# sensorion_board.net
KiCad netlist of a schematic drawn in Altium Designer
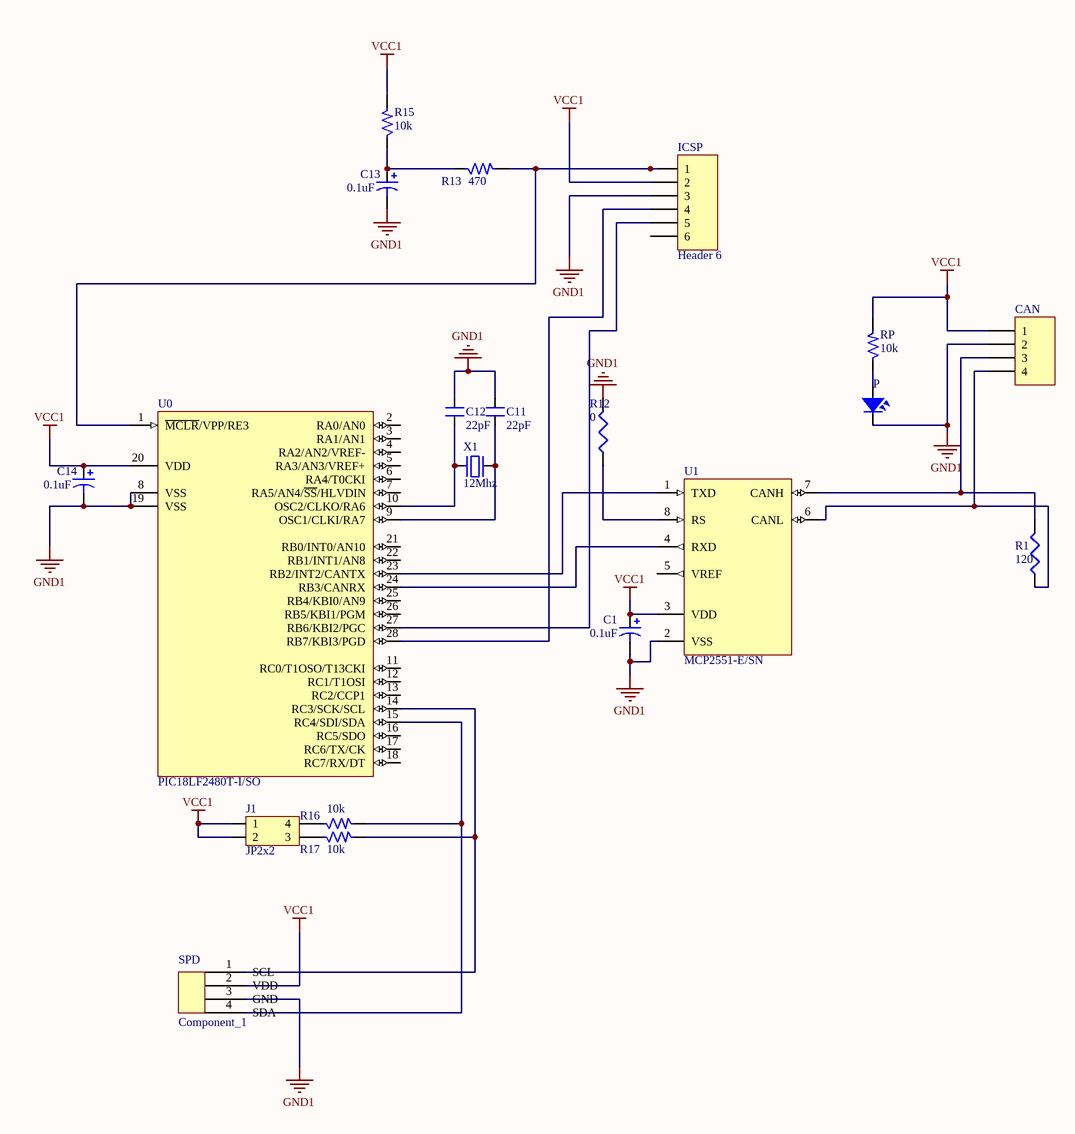
[diagram p0: sensorion_board.SchDoc]

(export (version "E")
  (design (tool "Eeschema 10.0.6"))
  (components
    (comp (ref "C1")
      (value "0.1uF")
      (footprint "C0805")
      (description "Polarized Capacitor (Surface Mount)")
      (fields (field (name "Comment") "Cap Pol3") (field (name "PUBLISHER") "Altium Limited"))
      (libsource (lib "Miscellaneous Devices") (part "Cap Pol3"))
    )
    (comp (ref "C11")
      (value "22pF")
      (footprint "CN1")
      (description "Cremic For Xtal 1pF => 100pF")
      (libsource (lib "electronicvn-library1") (part "CN0"))
    )
    (comp (ref "C12")
      (value "22pF")
      (footprint "CN1")
      (description "Cremic For Xtal 1pF => 100pF")
      (libsource (lib "electronicvn-library1") (part "CN0"))
    )
    (comp (ref "C13")
      (value "0.1uF")
      (footprint "C0805")
      (description "Polarized Capacitor (Surface Mount)")
      (fields (field (name "Comment") "Cap Pol3") (field (name "PUBLISHER") "Altium Limited"))
      (libsource (lib "Miscellaneous Devices") (part "Cap Pol3"))
    )
    (comp (ref "C14")
      (value "0.1uF")
      (footprint "C0805")
      (description "Polarized Capacitor (Surface Mount)")
      (fields (field (name "Comment") "Cap Pol3") (field (name "PUBLISHER") "Altium Limited"))
      (libsource (lib "Miscellaneous Devices") (part "Cap Pol3"))
    )
    (comp (ref "CAN")
      (value "Header 4")
      (footprint "HDR1X4")
      (description "Header, 4-Pin")
      (fields (field (name "PUBLISHER") "Altium Limited"))
      (libsource (lib "Miscellaneous Connectors") (part "Header 4"))
    )
    (comp (ref "ICSP")
      (value "Header 6")
      (footprint "HDR1X6")
      (description "Header, 6-Pin")
      (fields (field (name "PUBLISHER") "Altium Limited"))
      (libsource (lib "Miscellaneous Connectors") (part "Header 6"))
    )
    (comp (ref "J1")
      (value "JP2x2")
      (footprint "JP2-C2T")
      (description "WR-PHD 2.54 mm Dual Socket Header")
      (fields
        (field (name "MANUFACTURER") "Würth Elektronik eiSos GmbH")
        (field (name "PARTNO") "61300421821")
        (field (name "CREATED BY") "Karrer Zheng")
      )
      (libsource (lib "LIBRARY") (part "JP2x2"))
    )
    (comp (ref "P")
      (value "LED")
      (footprint "LED-3MM-YELLOW")
      (description "LED Single colour Green and Red")
      (libsource (lib "LIBRARY") (part "LED"))
    )
    (comp (ref "R1")
      (value "120")
      (footprint "J1-0603")
      (description "Resistor")
      (fields (field (name "Comment") "Res3") (field (name "PUBLISHER") "Altium Limited"))
      (libsource (lib "Miscellaneous Devices") (part "Res3"))
    )
    (comp (ref "R12")
      (value "0")
      (footprint "J1-0603")
      (description "Resistor")
      (fields (field (name "Comment") "Res3") (field (name "PUBLISHER") "Altium Limited"))
      (libsource (lib "Miscellaneous Devices") (part "Res3"))
    )
    (comp (ref "R13")
      (value "470")
      (footprint "SM-RES-1206")
      (description "Resistor 1/4W")
      (libsource (lib "electronicvn-library1") (part "R"))
    )
    (comp (ref "R15")
      (value "10k")
      (footprint "SM-RES-1206")
      (description "Resistor 1/4W")
      (libsource (lib "electronicvn-library1") (part "R"))
    )
    (comp (ref "R16")
      (value "10k")
      (footprint "SM-RES-1206")
      (description "Resistor 1/4W")
      (libsource (lib "electronicvn-library1") (part "R"))
    )
    (comp (ref "R17")
      (value "10k")
      (footprint "SM-RES-1206")
      (description "Resistor 1/4W")
      (libsource (lib "electronicvn-library1") (part "R"))
    )
    (comp (ref "RP")
      (value "10k")
      (footprint "SM-RES-1206")
      (description "Resistor 1/4W")
      (libsource (lib "electronicvn-library1") (part "R"))
    )
    (comp (ref "SPD")
      (value "Component_1")
      (footprint "PCBComponent_1")
      (libsource (lib "spd800") (part "Component_1"))
    )
    (comp (ref "U0")
      (value "PIC18LF2480T-I/SO")
      (footprint "SOIC-SO28_N")
      (fields (field (name "PUBLISHER") "Altium Limited"))
      (libsource (lib "Microchip Microcontroller 8-Bit PIC18") (part "PIC18LF2480T-I/SO"))
    )
    (comp (ref "U1")
      (value "MCP2551-E/SN")
      (footprint "SOIC-SN8_N")
      (description "High-Speed CAN Transceiver, 8-Pin SOIC, Extended Temperature")
      (fields (field (name "PUBLISHER") "Altium Limited"))
      (libsource (lib "Microchip Interface") (part "MCP2551-E/SN"))
    )
    (comp (ref "X1")
      (value "12Mhz")
      (footprint "XT2")
      (description "Crystal, 32.768 KHz, -40 to 85 degC, 3.2 x 1.5 x 0.9 mm SMD")
      (libsource (lib "LIBRARY") (part "XT2"))
    )
  )
  (nets
    (net (code "1") (name "GND1") (class "Default")
      (node (ref "C1") (pin "2") (pinfunction "2_2") (pintype "passive"))
      (node (ref "C11") (pin "2") (pinfunction "2_2") (pintype "passive"))
      (node (ref "C12") (pin "2") (pinfunction "2_2") (pintype "passive"))
      (node (ref "C13") (pin "2") (pinfunction "2_2") (pintype "passive"))
      (node (ref "C14") (pin "2") (pinfunction "2_2") (pintype "passive"))
      (node (ref "CAN") (pin "2") (pinfunction "2_2") (pintype "passive"))
      (node (ref "ICSP") (pin "3") (pinfunction "3_3") (pintype "passive"))
      (node (ref "P") (pin "2") (pinfunction "2_2") (pintype "passive"))
      (node (ref "R12") (pin "2") (pinfunction "2_2") (pintype "passive"))
      (node (ref "SPD") (pin "3") (pinfunction "GND_3") (pintype "passive"))
      (node (ref "U0") (pin "19") (pinfunction "VSS_19") (pintype "power_in"))
      (node (ref "U0") (pin "8") (pinfunction "VSS_8") (pintype "power_in"))
      (node (ref "U1") (pin "2") (pinfunction "VSS_2") (pintype "power_in"))
    )
    (net (code "2") (name "Net-(C13-Pad1)") (class "Default")
      (node (ref "C13") (pin "1") (pinfunction "1_1") (pintype "passive"))
      (node (ref "R13") (pin "1") (pinfunction "1_1") (pintype "passive"))
      (node (ref "R15") (pin "1") (pinfunction "1_1") (pintype "passive"))
    )
    (net (code "3") (name "Net-(J1-Pad3)") (class "Default")
      (node (ref "J1") (pin "3") (pinfunction "3_3") (pintype "passive"))
      (node (ref "R17") (pin "1") (pinfunction "1_1") (pintype "passive"))
    )
    (net (code "4") (name "Net-(J1-Pad4)") (class "Default")
      (node (ref "J1") (pin "4") (pinfunction "4_4") (pintype "passive"))
      (node (ref "R16") (pin "1") (pinfunction "1_1") (pintype "passive"))
    )
    (net (code "5") (name "Net-(P-Pad1)") (class "Default")
      (node (ref "P") (pin "1") (pinfunction "1_1") (pintype "passive"))
      (node (ref "RP") (pin "1") (pinfunction "1_1") (pintype "passive"))
    )
    (net (code "6") (name "Net-(SPD-SCL)") (class "Default")
      (node (ref "R17") (pin "2") (pinfunction "2_2") (pintype "passive"))
      (node (ref "SPD") (pin "1") (pinfunction "SCL_1") (pintype "passive"))
      (node (ref "U0") (pin "14") (pinfunction "RC3/SCK/SCL_14") (pintype "bidirectional"))
    )
    (net (code "7") (name "Net-(SPD-SDA)") (class "Default")
      (node (ref "R16") (pin "2") (pinfunction "2_2") (pintype "passive"))
      (node (ref "SPD") (pin "4") (pinfunction "SDA_4") (pintype "passive"))
      (node (ref "U0") (pin "15") (pinfunction "RC4/SDI/SDA_15") (pintype "bidirectional"))
    )
    (net (code "8") (name "Net-(U0-OSC1{slash}CLKI{slash}RA7)") (class "Default")
      (node (ref "C11") (pin "1") (pinfunction "1_1") (pintype "passive"))
      (node (ref "U0") (pin "9") (pinfunction "OSC1/CLKI/RA7_9") (pintype "bidirectional"))
      (node (ref "X1") (pin "2") (pinfunction "2_2") (pintype "passive"))
    )
    (net (code "9") (name "Net-(U0-OSC2{slash}CLKO{slash}RA6)") (class "Default")
      (node (ref "C12") (pin "1") (pinfunction "1_1") (pintype "passive"))
      (node (ref "U0") (pin "10") (pinfunction "OSC2/CLKO/RA6_10") (pintype "bidirectional"))
      (node (ref "X1") (pin "1") (pinfunction "1_1") (pintype "passive"))
    )
    (net (code "10") (name "Net-(U0-RB2{slash}INT2{slash}CANTX)") (class "Default")
      (node (ref "U0") (pin "23") (pinfunction "RB2/INT2/CANTX_23") (pintype "bidirectional"))
      (node (ref "U1") (pin "1") (pinfunction "TXD_1") (pintype "input"))
    )
    (net (code "11") (name "Net-(U0-RB3{slash}CANRX)") (class "Default")
      (node (ref "U0") (pin "24") (pinfunction "RB3/CANRX_24") (pintype "bidirectional"))
      (node (ref "U1") (pin "4") (pinfunction "RXD_4") (pintype "output"))
    )
    (net (code "12") (name "Net-(U0-RB6{slash}KBI2{slash}PGC)") (class "Default")
      (node (ref "ICSP") (pin "5") (pinfunction "5_5") (pintype "passive"))
      (node (ref "U0") (pin "27") (pinfunction "RB6/KBI2/PGC_27") (pintype "bidirectional"))
    )
    (net (code "13") (name "Net-(U0-RB7{slash}KBI3{slash}PGD)") (class "Default")
      (node (ref "ICSP") (pin "4") (pinfunction "4_4") (pintype "passive"))
      (node (ref "U0") (pin "28") (pinfunction "RB7/KBI3/PGD_28") (pintype "bidirectional"))
    )
    (net (code "14") (name "Net-(U0-~{MCLR}{slash}VPP{slash}RE3)") (class "Default")
      (node (ref "ICSP") (pin "1") (pinfunction "1_1") (pintype "passive"))
      (node (ref "R13") (pin "2") (pinfunction "2_2") (pintype "passive"))
      (node (ref "U0") (pin "1") (pinfunction "~{MCLR}/VPP/RE3_1") (pintype "input"))
    )
    (net (code "15") (name "Net-(U1-CANH)") (class "Default")
      (node (ref "CAN") (pin "3") (pinfunction "3_3") (pintype "passive"))
      (node (ref "R1") (pin "2") (pinfunction "2_2") (pintype "passive"))
      (node (ref "U1") (pin "7") (pinfunction "CANH_7") (pintype "bidirectional"))
    )
    (net (code "16") (name "Net-(U1-CANL)") (class "Default")
      (node (ref "CAN") (pin "4") (pinfunction "4_4") (pintype "passive"))
      (node (ref "R1") (pin "1") (pinfunction "1_1") (pintype "passive"))
      (node (ref "U1") (pin "6") (pinfunction "CANL_6") (pintype "bidirectional"))
    )
    (net (code "17") (name "Net-(U1-RS)") (class "Default")
      (node (ref "R12") (pin "1") (pinfunction "1_1") (pintype "passive"))
      (node (ref "U1") (pin "8") (pinfunction "RS_8") (pintype "input"))
    )
    (net (code "18") (name "VCC1") (class "Default")
      (node (ref "C1") (pin "1") (pinfunction "1_1") (pintype "passive"))
      (node (ref "C14") (pin "1") (pinfunction "1_1") (pintype "passive"))
      (node (ref "CAN") (pin "1") (pinfunction "1_1") (pintype "passive"))
      (node (ref "ICSP") (pin "2") (pinfunction "2_2") (pintype "passive"))
      (node (ref "J1") (pin "1") (pinfunction "1_1") (pintype "passive"))
      (node (ref "J1") (pin "2") (pinfunction "2_2") (pintype "passive"))
      (node (ref "R15") (pin "2") (pinfunction "2_2") (pintype "passive"))
      (node (ref "RP") (pin "2") (pinfunction "2_2") (pintype "passive"))
      (node (ref "SPD") (pin "2") (pinfunction "VDD_2") (pintype "passive"))
      (node (ref "U0") (pin "20") (pinfunction "VDD_20") (pintype "power_in"))
      (node (ref "U1") (pin "3") (pinfunction "VDD_3") (pintype "power_in"))
    )
    (net (code "19") (name "unconnected-(ICSP-Pad6)") (class "Default")
      (node (ref "ICSP") (pin "6") (pinfunction "6_6") (pintype "passive"))
    )
    (net (code "20") (name "unconnected-(U0-RA0{slash}AN0-Pad2)") (class "Default")
      (node (ref "U0") (pin "2") (pinfunction "RA0/AN0_2") (pintype "bidirectional"))
    )
    (net (code "21") (name "unconnected-(U0-RA1{slash}AN1-Pad3)") (class "Default")
      (node (ref "U0") (pin "3") (pinfunction "RA1/AN1_3") (pintype "bidirectional"))
    )
    (net (code "22") (name "unconnected-(U0-RA2{slash}AN2{slash}VREF--Pad4)") (class "Default")
      (node (ref "U0") (pin "4") (pinfunction "RA2/AN2/VREF-_4") (pintype "bidirectional"))
    )
    (net (code "23") (name "unconnected-(U0-RA3{slash}AN3{slash}VREF+-Pad5)") (class "Default")
      (node (ref "U0") (pin "5") (pinfunction "RA3/AN3/VREF+_5") (pintype "bidirectional"))
    )
    (net (code "24") (name "unconnected-(U0-RA4{slash}T0CKI-Pad6)") (class "Default")
      (node (ref "U0") (pin "6") (pinfunction "RA4/T0CKI_6") (pintype "bidirectional"))
    )
    (net (code "25") (name "unconnected-(U0-RA5{slash}AN4{slash}~{SS}{slash}HLVDIN-Pad7)") (class "Default")
      (node (ref "U0") (pin "7") (pinfunction "RA5/AN4/~{SS}/HLVDIN_7") (pintype "bidirectional"))
    )
    (net (code "26") (name "unconnected-(U0-RB0{slash}INT0{slash}AN10-Pad21)") (class "Default")
      (node (ref "U0") (pin "21") (pinfunction "RB0/INT0/AN10_21") (pintype "bidirectional"))
    )
    (net (code "27") (name "unconnected-(U0-RB1{slash}INT1{slash}AN8-Pad22)") (class "Default")
      (node (ref "U0") (pin "22") (pinfunction "RB1/INT1/AN8_22") (pintype "bidirectional"))
    )
    (net (code "28") (name "unconnected-(U0-RB4{slash}KBI0{slash}AN9-Pad25)") (class "Default")
      (node (ref "U0") (pin "25") (pinfunction "RB4/KBI0/AN9_25") (pintype "bidirectional"))
    )
    (net (code "29") (name "unconnected-(U0-RB5{slash}KBI1{slash}PGM-Pad26)") (class "Default")
      (node (ref "U0") (pin "26") (pinfunction "RB5/KBI1/PGM_26") (pintype "bidirectional"))
    )
    (net (code "30") (name "unconnected-(U0-RC0{slash}T1OSO{slash}T13CKI-Pad11)") (class "Default")
      (node (ref "U0") (pin "11") (pinfunction "RC0/T1OSO/T13CKI_11") (pintype "bidirectional"))
    )
    (net (code "31") (name "unconnected-(U0-RC1{slash}T1OSI-Pad12)") (class "Default")
      (node (ref "U0") (pin "12") (pinfunction "RC1/T1OSI_12") (pintype "bidirectional"))
    )
    (net (code "32") (name "unconnected-(U0-RC2{slash}CCP1-Pad13)") (class "Default")
      (node (ref "U0") (pin "13") (pinfunction "RC2/CCP1_13") (pintype "bidirectional"))
    )
    (net (code "33") (name "unconnected-(U0-RC5{slash}SDO-Pad16)") (class "Default")
      (node (ref "U0") (pin "16") (pinfunction "RC5/SDO_16") (pintype "bidirectional"))
    )
    (net (code "34") (name "unconnected-(U0-RC6{slash}TX{slash}CK-Pad17)") (class "Default")
      (node (ref "U0") (pin "17") (pinfunction "RC6/TX/CK_17") (pintype "bidirectional"))
    )
    (net (code "35") (name "unconnected-(U0-RC7{slash}RX{slash}DT-Pad18)") (class "Default")
      (node (ref "U0") (pin "18") (pinfunction "RC7/RX/DT_18") (pintype "bidirectional"))
    )
    (net (code "36") (name "unconnected-(U1-VREF-Pad5)") (class "Default")
      (node (ref "U1") (pin "5") (pinfunction "VREF_5") (pintype "output"))
    )
  )
)
